# SkyNetV3_1.net
KiCad netlist of a schematic drawn in EAGLE
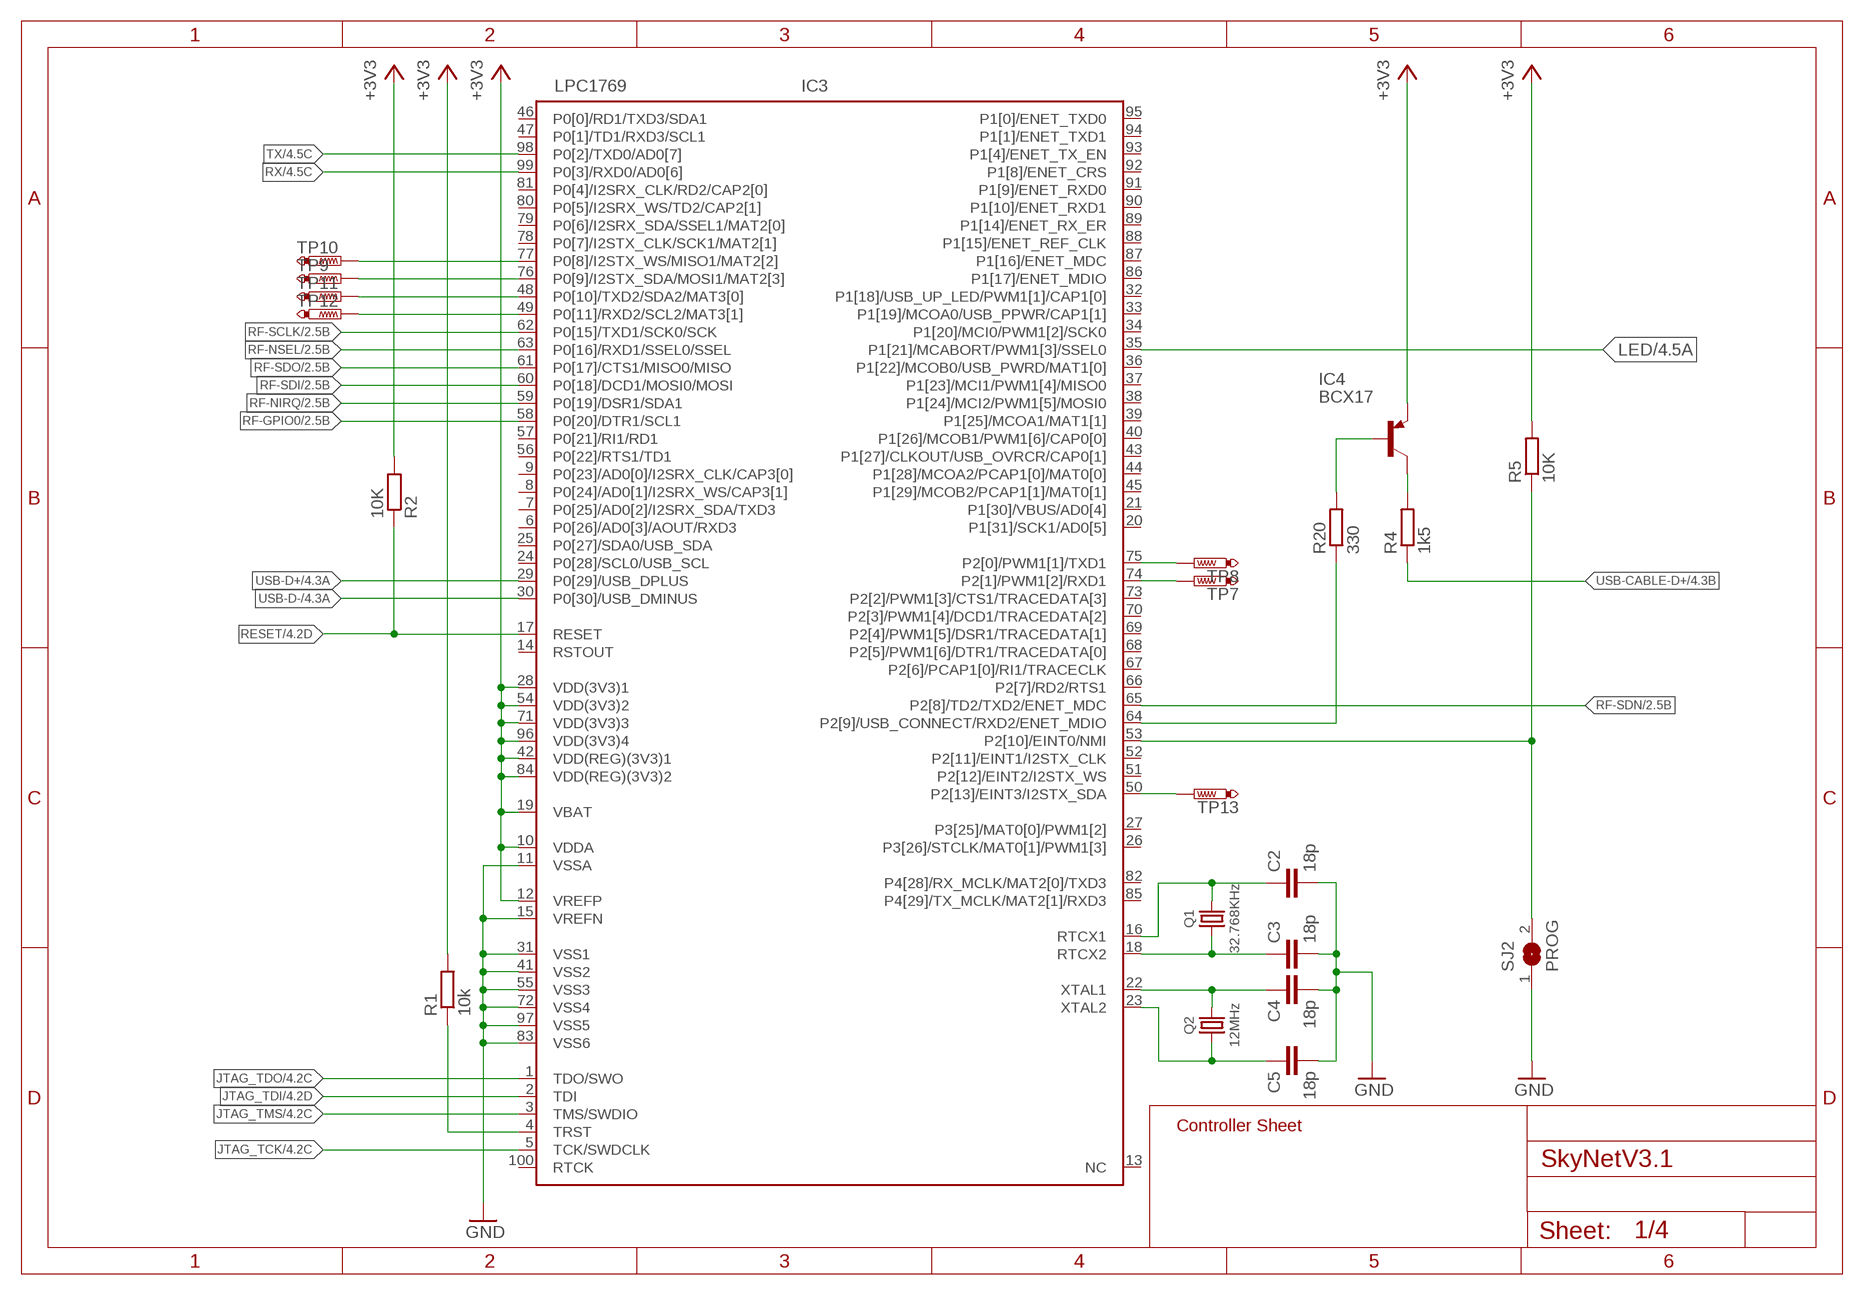
[diagram p0: schematic, sheet 1]
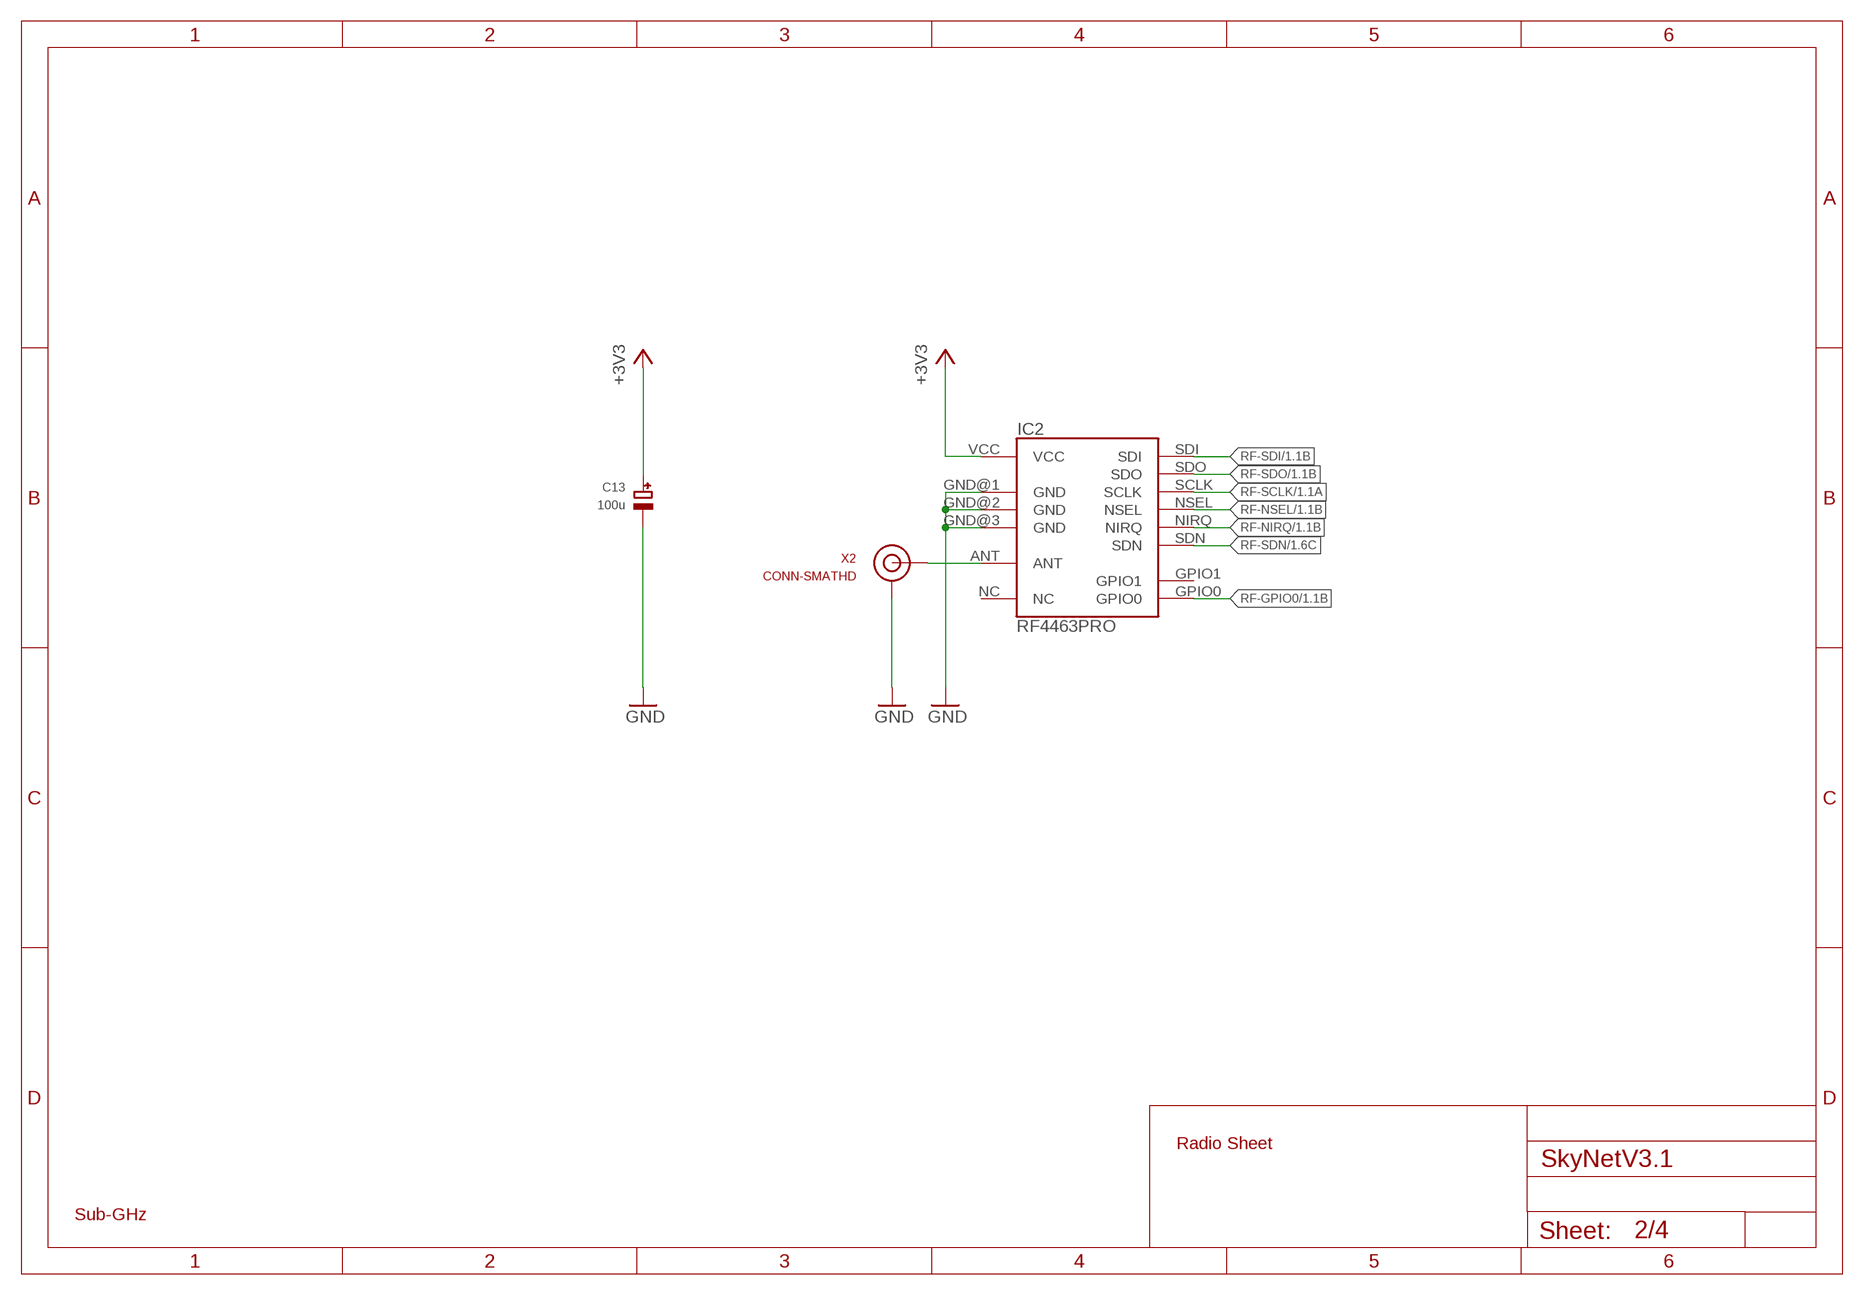
[diagram p1: schematic, sheet 2]
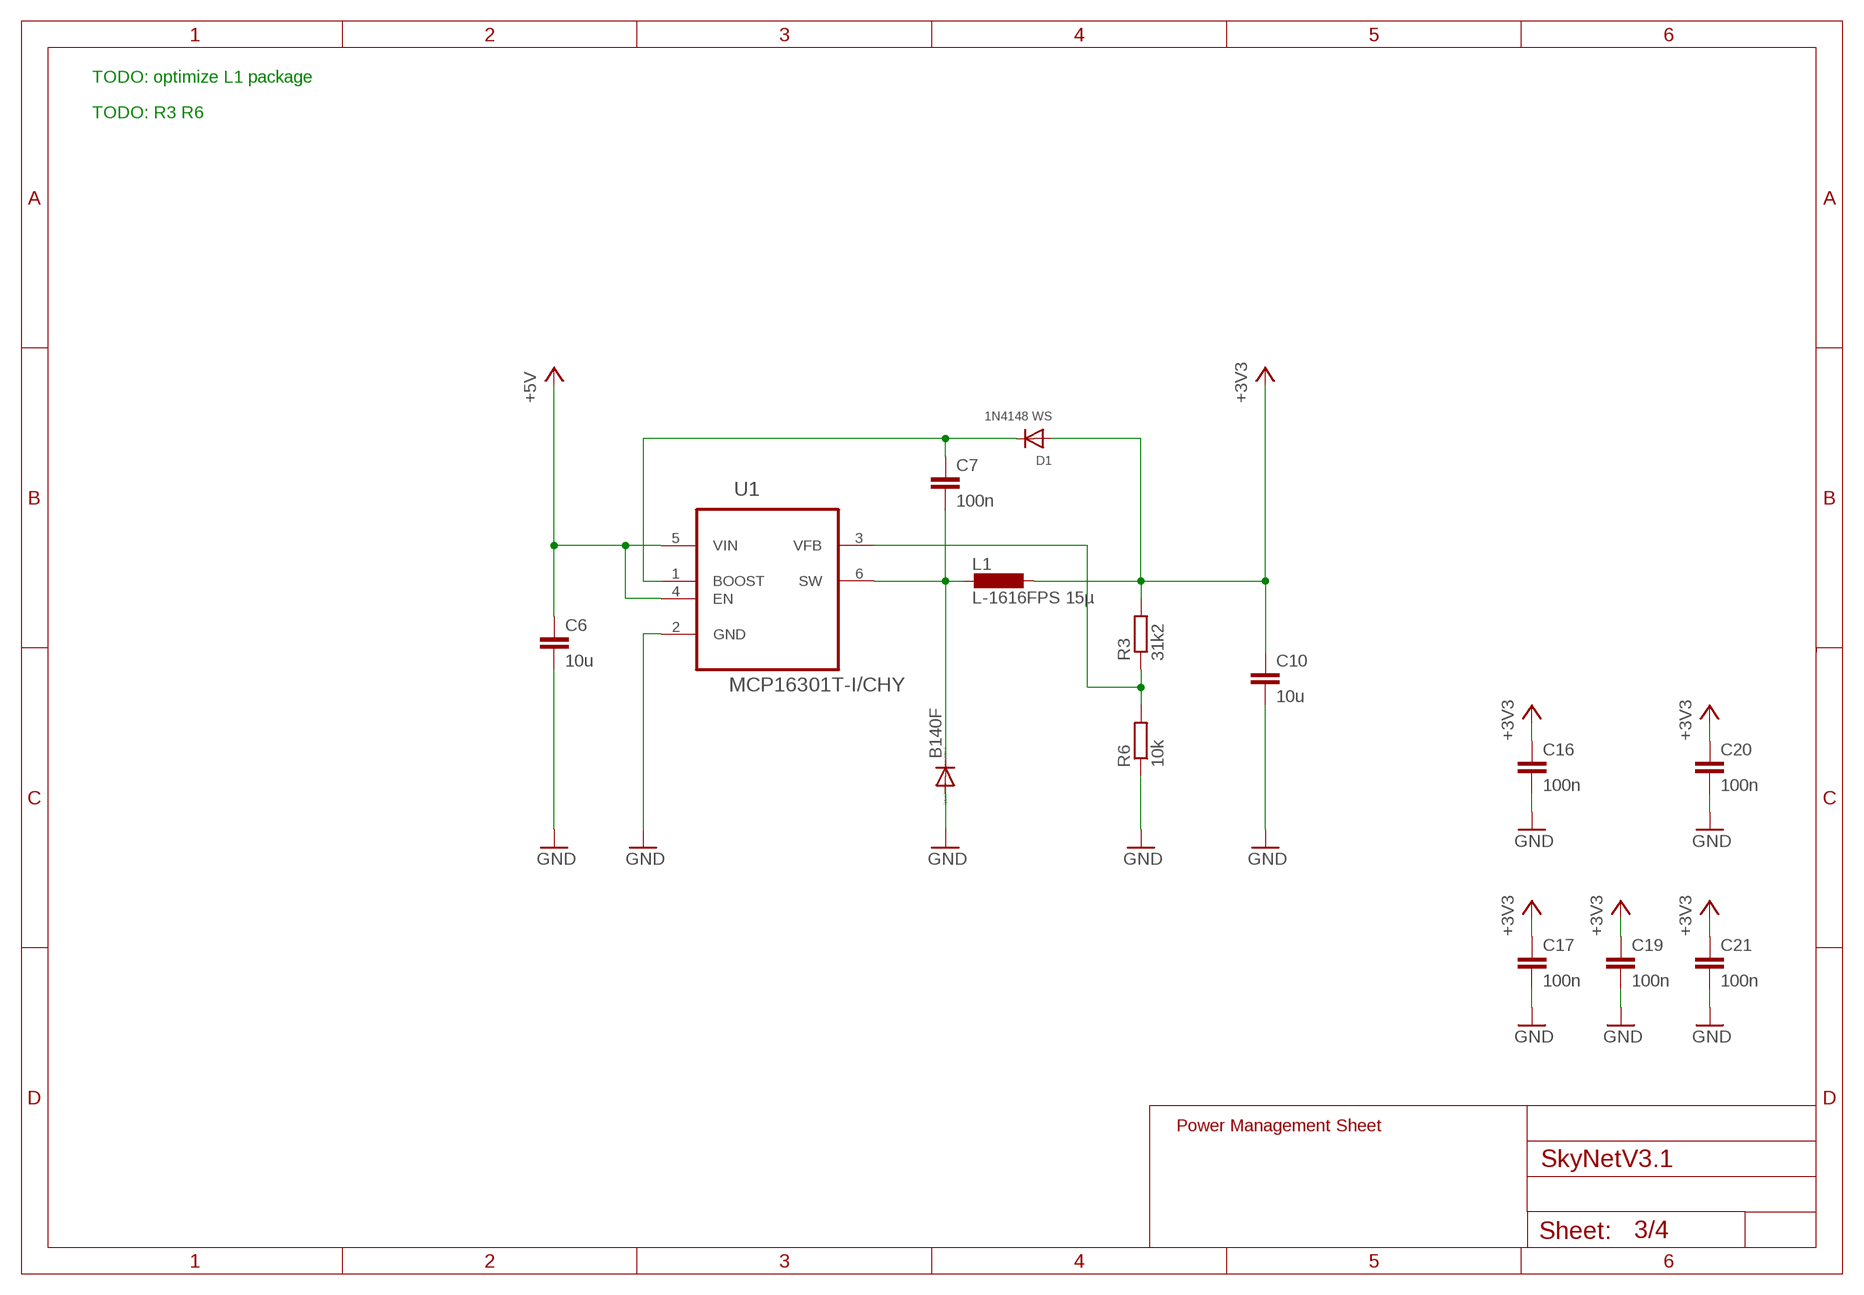
[diagram p2: schematic, sheet 3]
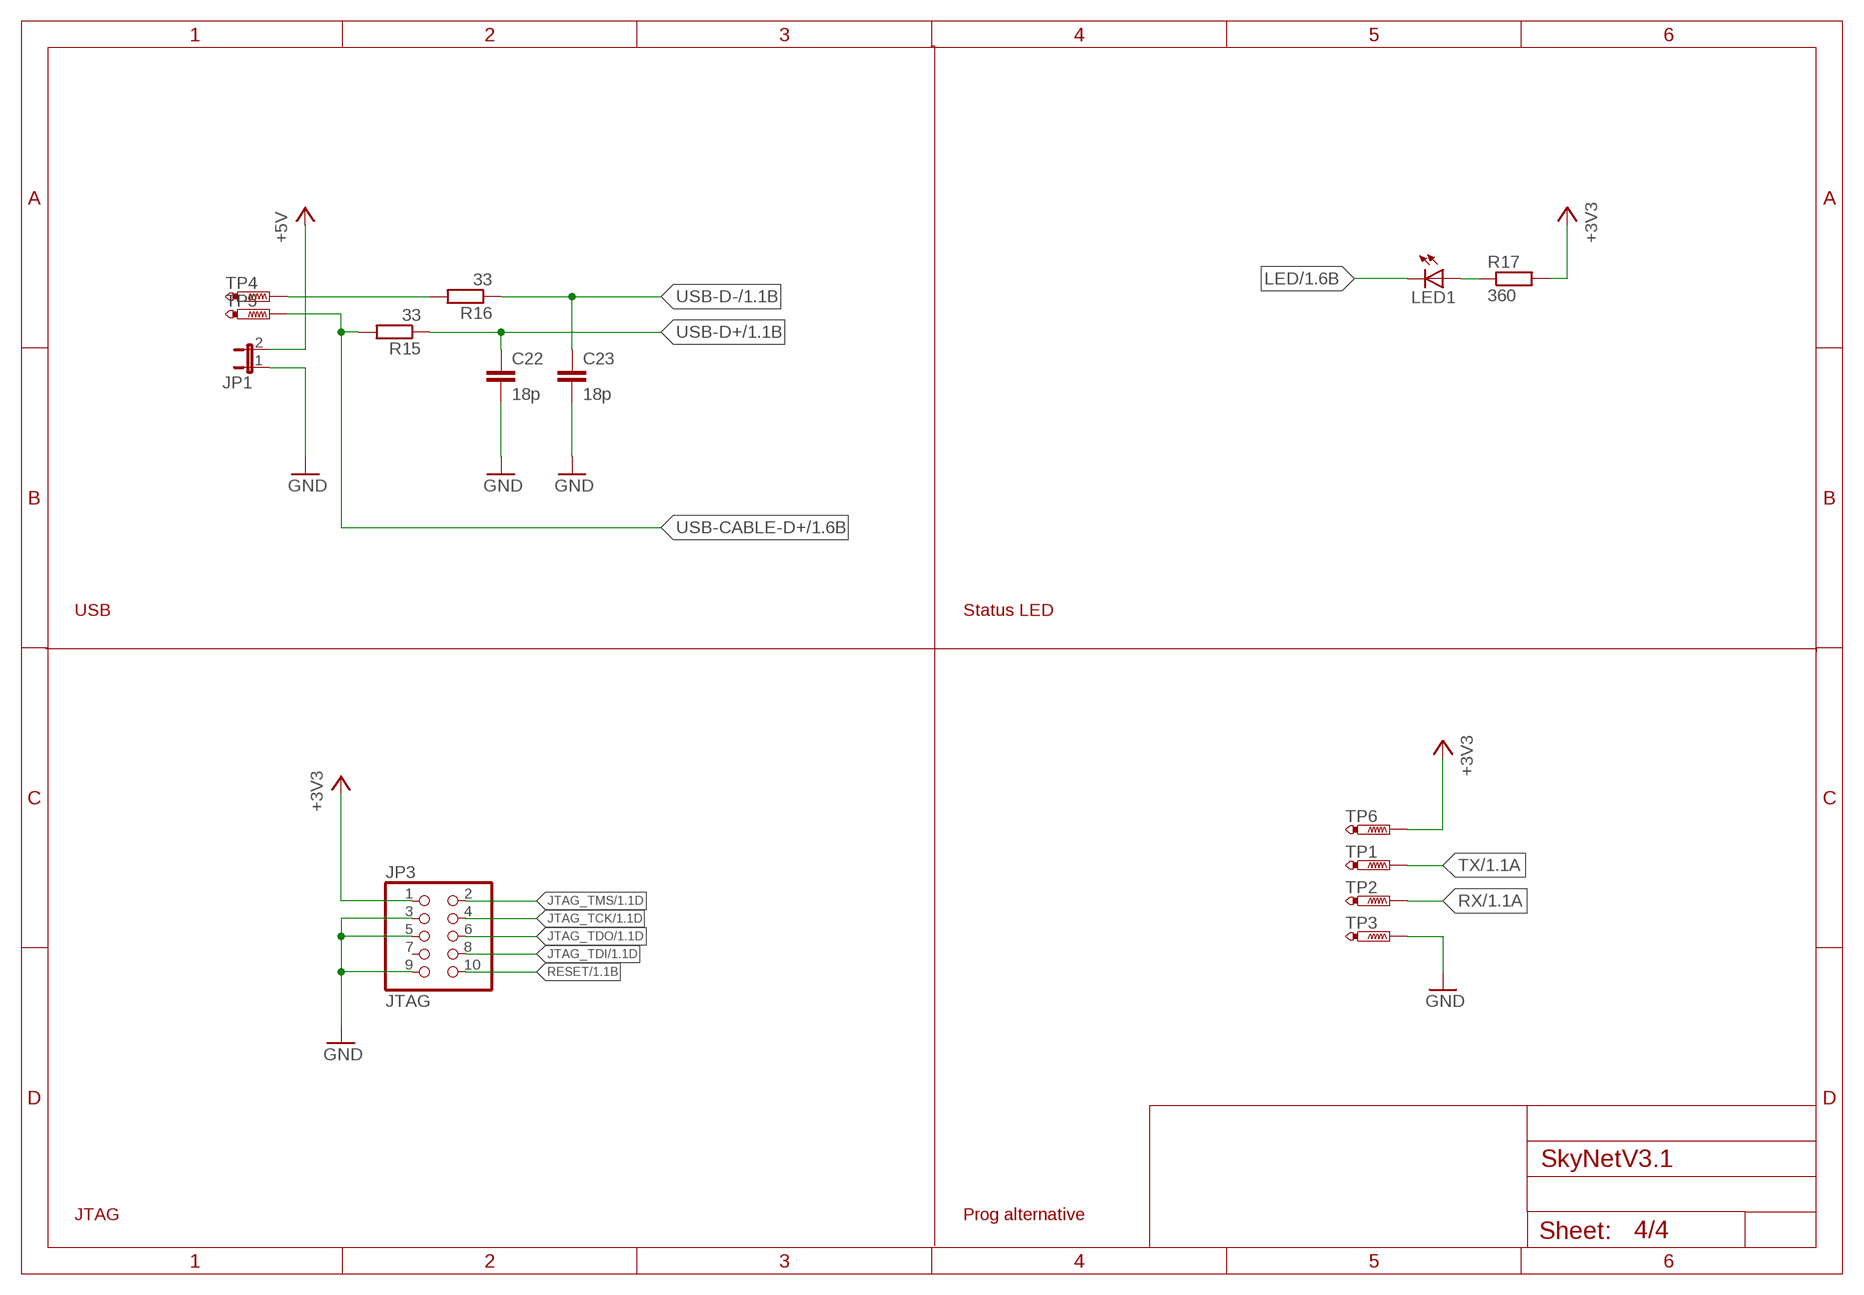
[diagram p3: schematic, sheet 4]

(export (version "E")
  (design (tool "Eeschema 10.0.6"))
  (components
    (comp (ref "C2")
      (value "18p")
      (footprint "eagle-import:C0603")
      (libsource (lib "eagle-import") (part "C-EUC0603"))
    )
    (comp (ref "C3")
      (value "18p")
      (footprint "eagle-import:C0603")
      (libsource (lib "eagle-import") (part "C-EUC0603"))
    )
    (comp (ref "C4")
      (value "18p")
      (footprint "eagle-import:C0603")
      (libsource (lib "eagle-import") (part "C-EUC0603"))
    )
    (comp (ref "C5")
      (value "18p")
      (footprint "eagle-import:C0603")
      (libsource (lib "eagle-import") (part "C-EUC0603"))
    )
    (comp (ref "IC3")
      (value "LPC1769")
      (footprint "eagle-import:LQFP100-14X14")
      (libsource (lib "eagle-import") (part "LPC1768"))
    )
    (comp (ref "IC4")
      (value "BCX17")
      (footprint "eagle-import:SOT23")
      (libsource (lib "eagle-import") (part "BCX17"))
    )
    (comp (ref "Q1")
      (value "32.768KHz")
      (footprint "eagle-import:XTAL_49_18")
      (libsource (lib "eagle-import") (part "XTAL2-PAD"))
    )
    (comp (ref "Q2")
      (value "12MHz")
      (footprint "eagle-import:XTAL_50_32")
      (libsource (lib "eagle-import") (part "XTAL4-PAD"))
    )
    (comp (ref "R1")
      (value "10k")
      (footprint "eagle-import:R0603")
      (libsource (lib "eagle-import") (part "R-EU_R0603"))
    )
    (comp (ref "R2")
      (value "10K")
      (footprint "eagle-import:R0603")
      (libsource (lib "eagle-import") (part "R-EU_R0603"))
    )
    (comp (ref "R4")
      (value "1k5")
      (footprint "eagle-import:R0603")
      (libsource (lib "eagle-import") (part "R-EU_R0603"))
    )
    (comp (ref "R5")
      (value "10K")
      (footprint "eagle-import:R0603")
      (libsource (lib "eagle-import") (part "R-EU_R0603"))
    )
    (comp (ref "R20")
      (value "330")
      (footprint "eagle-import:R0603")
      (libsource (lib "eagle-import") (part "R-EU_R0603"))
    )
    (comp (ref "SJ2")
      (value "PROG")
      (footprint "eagle-import:SJ")
      (libsource (lib "eagle-import") (part "SJ"))
    )
    (comp (ref "TP7")
      (value "PTR1B1,27")
      (footprint "eagle-import:B1,27")
      (libsource (lib "eagle-import") (part "PTR1B1,27"))
    )
    (comp (ref "TP8")
      (value "PTR1B1,27")
      (footprint "eagle-import:B1,27")
      (libsource (lib "eagle-import") (part "PTR1B1,27"))
    )
    (comp (ref "TP9")
      (value "PTR1B1,27")
      (footprint "eagle-import:B1,27")
      (libsource (lib "eagle-import") (part "PTR1B1,27"))
    )
    (comp (ref "TP10")
      (value "PTR1B1,27")
      (footprint "eagle-import:B1,27")
      (libsource (lib "eagle-import") (part "PTR1B1,27"))
    )
    (comp (ref "TP11")
      (value "PTR1B1,27")
      (footprint "eagle-import:B1,27")
      (libsource (lib "eagle-import") (part "PTR1B1,27"))
    )
    (comp (ref "TP12")
      (value "PTR1B1,27")
      (footprint "eagle-import:B1,27")
      (libsource (lib "eagle-import") (part "PTR1B1,27"))
    )
    (comp (ref "TP13")
      (value "PTR1B1,27")
      (footprint "eagle-import:B1,27")
      (libsource (lib "eagle-import") (part "PTR1B1,27"))
    )
    (comp (ref "C13")
      (value "100u")
      (footprint "eagle-import:EIA6032-28_C-W")
      (libsource (lib "eagle-import") (part "CAP_TANTALUMC/6032_WAVE"))
    )
    (comp (ref "IC2")
      (value "RF4463PRO")
      (footprint "eagle-import:STD_BOARD")
      (libsource (lib "eagle-import") (part "RF4463PRO"))
    )
    (comp (ref "X2")
      (value "CONN-SMATHD")
      (footprint "eagle-import:SMA-THD")
      (libsource (lib "eagle-import") (part "CONN-SMATHD"))
    )
    (comp (ref "C22")
      (value "18p")
      (footprint "eagle-import:C0603")
      (libsource (lib "eagle-import") (part "C-EUC0603"))
    )
    (comp (ref "C23")
      (value "18p")
      (footprint "eagle-import:C0603")
      (libsource (lib "eagle-import") (part "C-EUC0603"))
    )
    (comp (ref "JP1")
      (value "JP1E")
      (footprint "eagle-import:JP1")
      (libsource (lib "eagle-import") (part "JP1E"))
    )
    (comp (ref "JP3")
      (value "JTAG")
      (footprint "eagle-import:2X05_1.27MM_SMT")
      (libsource (lib "eagle-import") (part "HEADER-2X51.27MM"))
    )
    (comp (ref "LED1")
      (value "LEDCHIP-LED0805")
      (footprint "eagle-import:CHIP-LED0805")
      (libsource (lib "eagle-import") (part "LEDCHIP-LED0805"))
    )
    (comp (ref "R15")
      (value "33")
      (footprint "eagle-import:R0603")
      (libsource (lib "eagle-import") (part "R-EU_R0603"))
    )
    (comp (ref "R16")
      (value "33")
      (footprint "eagle-import:R0603")
      (libsource (lib "eagle-import") (part "R-EU_R0603"))
    )
    (comp (ref "R17")
      (value "360")
      (footprint "eagle-import:R0603")
      (libsource (lib "eagle-import") (part "R-EU_R0603"))
    )
    (comp (ref "TP1")
      (value "PTR1B1,27")
      (footprint "eagle-import:B1,27")
      (libsource (lib "eagle-import") (part "PTR1B1,27"))
    )
    (comp (ref "TP2")
      (value "PTR1B1,27")
      (footprint "eagle-import:B1,27")
      (libsource (lib "eagle-import") (part "PTR1B1,27"))
    )
    (comp (ref "TP3")
      (value "PTR1B2,54")
      (footprint "eagle-import:B2,54")
      (libsource (lib "eagle-import") (part "PTR1B2,54"))
    )
    (comp (ref "TP4")
      (value "PTR1B1,27")
      (footprint "eagle-import:B1,27")
      (libsource (lib "eagle-import") (part "PTR1B1,27"))
    )
    (comp (ref "TP5")
      (value "PTR1B1,27")
      (footprint "eagle-import:B1,27")
      (libsource (lib "eagle-import") (part "PTR1B1,27"))
    )
    (comp (ref "TP6")
      (value "PTR1B2,54")
      (footprint "eagle-import:B2,54")
      (libsource (lib "eagle-import") (part "PTR1B2,54"))
    )
    (comp (ref "B140F")
      (value "DIODE-DO214AC")
      (footprint "eagle-import:DO214AC")
      (libsource (lib "eagle-import") (part "DIODE-DO214AC"))
    )
    (comp (ref "C6")
      (value "10u")
      (footprint "eagle-import:C0805")
      (libsource (lib "eagle-import") (part "C-EUC0805"))
    )
    (comp (ref "C7")
      (value "100n")
      (footprint "eagle-import:C0603")
      (libsource (lib "eagle-import") (part "C-EUC0603"))
    )
    (comp (ref "C10")
      (value "10u")
      (footprint "eagle-import:C0805")
      (libsource (lib "eagle-import") (part "C-EUC0805"))
    )
    (comp (ref "C16")
      (value "100n")
      (footprint "eagle-import:C0603")
      (libsource (lib "eagle-import") (part "C-EUC0603"))
    )
    (comp (ref "C17")
      (value "100n")
      (footprint "eagle-import:C0603")
      (libsource (lib "eagle-import") (part "C-EUC0603"))
    )
    (comp (ref "C19")
      (value "100n")
      (footprint "eagle-import:C0603")
      (libsource (lib "eagle-import") (part "C-EUC0603"))
    )
    (comp (ref "C20")
      (value "100n")
      (footprint "eagle-import:C0603")
      (libsource (lib "eagle-import") (part "C-EUC0603"))
    )
    (comp (ref "C21")
      (value "100n")
      (footprint "eagle-import:C0603")
      (libsource (lib "eagle-import") (part "C-EUC0603"))
    )
    (comp (ref "D1")
      (value "1N4148 WS")
      (footprint "eagle-import:SOD-323")
      (libsource (lib "eagle-import") (part "DIODESOD-323"))
    )
    (comp (ref "L1")
      (value "L-1616FPS 15µ")
      (footprint "eagle-import:LQH55D")
      (libsource (lib "eagle-import") (part "L-EU2220-LQH55D"))
    )
    (comp (ref "R3")
      (value "31k2")
      (footprint "eagle-import:R0603")
      (libsource (lib "eagle-import") (part "R-EU_R0603"))
    )
    (comp (ref "R6")
      (value "10k")
      (footprint "eagle-import:R0603")
      (libsource (lib "eagle-import") (part "R-EU_R0603"))
    )
    (comp (ref "U1")
      (value "MCP16301T-I/CHY")
      (footprint "eagle-import:SOT95P290X145-6N")
      (libsource (lib "eagle-import") (part "MCP16301T-I/CHY"))
    )
  )
  (nets
    (net (code "1") (name "+3V3") (class "Default")
      (node (ref "C10") (pin "1") (pinfunction "1_1") (pintype "passive"))
      (node (ref "C13") (pin "+") (pinfunction "+_+") (pintype "passive"))
      (node (ref "C16") (pin "1") (pinfunction "1_1") (pintype "passive"))
      (node (ref "C17") (pin "1") (pinfunction "1_1") (pintype "passive"))
      (node (ref "C19") (pin "1") (pinfunction "1_1") (pintype "passive"))
      (node (ref "C20") (pin "1") (pinfunction "1_1") (pintype "passive"))
      (node (ref "C21") (pin "1") (pinfunction "1_1") (pintype "passive"))
      (node (ref "D1") (pin "A") (pinfunction "A_A") (pintype "passive"))
      (node (ref "IC2") (pin "VCC") (pinfunction "VCC_VCC") (pintype "power_in"))
      (node (ref "IC3") (pin "10") (pinfunction "VDDA_10") (pintype "bidirectional"))
      (node (ref "IC3") (pin "12") (pinfunction "VREFP_12") (pintype "bidirectional"))
      (node (ref "IC3") (pin "19") (pinfunction "VBAT_19") (pintype "bidirectional"))
      (node (ref "IC3") (pin "28") (pinfunction "VDD(3V3)1_28") (pintype "bidirectional"))
      (node (ref "IC3") (pin "42") (pinfunction "VDD(REG)(3V3)1_42") (pintype "bidirectional"))
      (node (ref "IC3") (pin "54") (pinfunction "VDD(3V3)2_54") (pintype "bidirectional"))
      (node (ref "IC3") (pin "71") (pinfunction "VDD(3V3)3_71") (pintype "bidirectional"))
      (node (ref "IC3") (pin "84") (pinfunction "VDD(REG)(3V3)2_84") (pintype "bidirectional"))
      (node (ref "IC3") (pin "96") (pinfunction "VDD(3V3)4_96") (pintype "bidirectional"))
      (node (ref "IC4") (pin "2") (pinfunction "E_2") (pintype "passive"))
      (node (ref "JP3") (pin "1") (pinfunction "1_1") (pintype "passive"))
      (node (ref "L1") (pin "P$1") (pinfunction "1_P$1") (pintype "passive"))
      (node (ref "R1") (pin "2") (pinfunction "2_2") (pintype "passive"))
      (node (ref "R17") (pin "2") (pinfunction "2_2") (pintype "passive"))
      (node (ref "R2") (pin "2") (pinfunction "2_2") (pintype "passive"))
      (node (ref "R3") (pin "2") (pinfunction "2_2") (pintype "passive"))
      (node (ref "R5") (pin "2") (pinfunction "2_2") (pintype "passive"))
      (node (ref "TP6") (pin "TP") (pinfunction "TP_TP") (pintype "input"))
    )
    (net (code "2") (name "+5V") (class "Default")
      (node (ref "C6") (pin "1") (pinfunction "1_1") (pintype "passive"))
      (node (ref "JP1") (pin "2") (pinfunction "2_2") (pintype "passive"))
      (node (ref "U1") (pin "4") (pinfunction "EN_4") (pintype "input"))
      (node (ref "U1") (pin "5") (pinfunction "VIN_5") (pintype "input"))
    )
    (net (code "3") (name "GND") (class "Default")
      (node (ref "B140F") (pin "A") (pinfunction "A_A") (pintype "passive"))
      (node (ref "C10") (pin "2") (pinfunction "2_2") (pintype "passive"))
      (node (ref "C13") (pin "-") (pinfunction "-_-") (pintype "passive"))
      (node (ref "C16") (pin "2") (pinfunction "2_2") (pintype "passive"))
      (node (ref "C17") (pin "2") (pinfunction "2_2") (pintype "passive"))
      (node (ref "C19") (pin "2") (pinfunction "2_2") (pintype "passive"))
      (node (ref "C2") (pin "2") (pinfunction "2_2") (pintype "passive"))
      (node (ref "C20") (pin "2") (pinfunction "2_2") (pintype "passive"))
      (node (ref "C21") (pin "2") (pinfunction "2_2") (pintype "passive"))
      (node (ref "C22") (pin "2") (pinfunction "2_2") (pintype "passive"))
      (node (ref "C23") (pin "2") (pinfunction "2_2") (pintype "passive"))
      (node (ref "C3") (pin "2") (pinfunction "2_2") (pintype "passive"))
      (node (ref "C4") (pin "2") (pinfunction "2_2") (pintype "passive"))
      (node (ref "C5") (pin "2") (pinfunction "2_2") (pintype "passive"))
      (node (ref "C6") (pin "2") (pinfunction "2_2") (pintype "passive"))
      (node (ref "IC2") (pin "GND@1") (pinfunction "GND_GND@1") (pintype "power_in"))
      (node (ref "IC2") (pin "GND@2") (pinfunction "GND_GND@2") (pintype "power_in"))
      (node (ref "IC2") (pin "GND@3") (pinfunction "GND_GND@3") (pintype "power_in"))
      (node (ref "IC3") (pin "11") (pinfunction "VSSA_11") (pintype "bidirectional"))
      (node (ref "IC3") (pin "15") (pinfunction "VREFN_15") (pintype "bidirectional"))
      (node (ref "IC3") (pin "31") (pinfunction "VSS1_31") (pintype "bidirectional"))
      (node (ref "IC3") (pin "41") (pinfunction "VSS2_41") (pintype "bidirectional"))
      (node (ref "IC3") (pin "55") (pinfunction "VSS3_55") (pintype "bidirectional"))
      (node (ref "IC3") (pin "72") (pinfunction "VSS4_72") (pintype "bidirectional"))
      (node (ref "IC3") (pin "83") (pinfunction "VSS6_83") (pintype "bidirectional"))
      (node (ref "IC3") (pin "97") (pinfunction "VSS5_97") (pintype "bidirectional"))
      (node (ref "JP1") (pin "1") (pinfunction "1_1") (pintype "passive"))
      (node (ref "JP3") (pin "3") (pinfunction "3_3") (pintype "passive"))
      (node (ref "JP3") (pin "5") (pinfunction "5_5") (pintype "passive"))
      (node (ref "JP3") (pin "9") (pinfunction "9_9") (pintype "passive"))
      (node (ref "R6") (pin "1") (pinfunction "1_1") (pintype "passive"))
      (node (ref "SJ2") (pin "1") (pinfunction "1_1") (pintype "passive"))
      (node (ref "TP3") (pin "TP") (pinfunction "TP_TP") (pintype "input"))
      (node (ref "U1") (pin "2") (pinfunction "GND_2") (pintype "passive"))
      (node (ref "X2") (pin "GND@0") (pinfunction "GND_GND@0") (pintype "bidirectional"))
      (node (ref "X2") (pin "GND@1") (pinfunction "GND_GND@1") (pintype "bidirectional"))
      (node (ref "X2") (pin "GND@2") (pinfunction "GND_GND@2") (pintype "bidirectional"))
      (node (ref "X2") (pin "GND@3") (pinfunction "GND_GND@3") (pintype "bidirectional"))
    )
    (net (code "4") (name "JTAG_TCK") (class "Default")
      (node (ref "IC3") (pin "5") (pinfunction "TCK/SWDCLK_5") (pintype "bidirectional"))
      (node (ref "JP3") (pin "4") (pinfunction "4_4") (pintype "passive"))
    )
    (net (code "5") (name "JTAG_TDI") (class "Default")
      (node (ref "IC3") (pin "2") (pinfunction "TDI_2") (pintype "bidirectional"))
      (node (ref "JP3") (pin "8") (pinfunction "8_8") (pintype "passive"))
    )
    (net (code "6") (name "JTAG_TDO") (class "Default")
      (node (ref "IC3") (pin "1") (pinfunction "TDO/SWO_1") (pintype "bidirectional"))
      (node (ref "JP3") (pin "6") (pinfunction "6_6") (pintype "passive"))
    )
    (net (code "7") (name "JTAG_TMS") (class "Default")
      (node (ref "IC3") (pin "3") (pinfunction "TMS/SWDIO_3") (pintype "bidirectional"))
      (node (ref "JP3") (pin "2") (pinfunction "2_2") (pintype "passive"))
    )
    (net (code "8") (name "LED") (class "Default")
      (node (ref "IC3") (pin "35") (pinfunction "P1[21]/MCABORT/PWM1[3]/SSEL0_35") (pintype "bidirectional"))
      (node (ref "LED1") (pin "C") (pinfunction "C_C") (pintype "passive"))
    )
    (net (code "9") (name "Net-(IC3-P0[8]{slash}I2STX_WS{slash}MISO1{slash}MAT2[2])") (class "Default")
      (node (ref "IC3") (pin "77") (pinfunction "P0[8]/I2STX_WS/MISO1/MAT2[2]_77") (pintype "bidirectional"))
      (node (ref "TP10") (pin "TP") (pinfunction "TP_TP") (pintype "input"))
    )
    (net (code "10") (name "Net-(IC3-P0[9]{slash}I2STX_SDA{slash}MOSI1{slash}MAT2[3])") (class "Default")
      (node (ref "IC3") (pin "76") (pinfunction "P0[9]/I2STX_SDA/MOSI1/MAT2[3]_76") (pintype "bidirectional"))
      (node (ref "TP9") (pin "TP") (pinfunction "TP_TP") (pintype "input"))
    )
    (net (code "11") (name "Net-(IC3-P0[10]{slash}TXD2{slash}SDA2{slash}MAT3[0])") (class "Default")
      (node (ref "IC3") (pin "48") (pinfunction "P0[10]/TXD2/SDA2/MAT3[0]_48") (pintype "bidirectional"))
      (node (ref "TP11") (pin "TP") (pinfunction "TP_TP") (pintype "input"))
    )
    (net (code "12") (name "Net-(IC3-P0[11]{slash}RXD2{slash}SCL2{slash}MAT3[1])") (class "Default")
      (node (ref "IC3") (pin "49") (pinfunction "P0[11]/RXD2/SCL2/MAT3[1]_49") (pintype "bidirectional"))
      (node (ref "TP12") (pin "TP") (pinfunction "TP_TP") (pintype "input"))
    )
    (net (code "13") (name "Net-(IC3-P2[0]{slash}PWM1[1]{slash}TXD1)") (class "Default")
      (node (ref "IC3") (pin "75") (pinfunction "P2[0]/PWM1[1]/TXD1_75") (pintype "bidirectional"))
      (node (ref "TP8") (pin "TP") (pinfunction "TP_TP") (pintype "input"))
    )
    (net (code "14") (name "Net-(IC3-P2[1]{slash}PWM1[2]{slash}RXD1)") (class "Default")
      (node (ref "IC3") (pin "74") (pinfunction "P2[1]/PWM1[2]/RXD1_74") (pintype "bidirectional"))
      (node (ref "TP7") (pin "TP") (pinfunction "TP_TP") (pintype "input"))
    )
    (net (code "15") (name "Net-(IC3-P2[9]{slash}USB_CONNECT{slash}RXD2{slash}ENET_MDIO)") (class "Default")
      (node (ref "IC3") (pin "64") (pinfunction "P2[9]/USB_CONNECT/RXD2/ENET_MDIO_64") (pintype "bidirectional"))
      (node (ref "R20") (pin "1") (pinfunction "1_1") (pintype "passive"))
    )
    (net (code "16") (name "Net-(IC3-P2[10]{slash}EINT0{slash}NMI)") (class "Default")
      (node (ref "IC3") (pin "53") (pinfunction "P2[10]/EINT0/NMI_53") (pintype "bidirectional"))
      (node (ref "R5") (pin "1") (pinfunction "1_1") (pintype "passive"))
      (node (ref "SJ2") (pin "2") (pinfunction "2_2") (pintype "passive"))
    )
    (net (code "17") (name "Net-(IC3-P2[13]{slash}EINT3{slash}I2STX_SDA)") (class "Default")
      (node (ref "IC3") (pin "50") (pinfunction "P2[13]/EINT3/I2STX_SDA_50") (pintype "bidirectional"))
      (node (ref "TP13") (pin "TP") (pinfunction "TP_TP") (pintype "input"))
    )
    (net (code "18") (name "Net-(IC3-RTCX1)") (class "Default")
      (node (ref "C2") (pin "1") (pinfunction "1_1") (pintype "passive"))
      (node (ref "IC3") (pin "16") (pinfunction "RTCX1_16") (pintype "bidirectional"))
      (node (ref "Q1") (pin "2") (pinfunction "2_2") (pintype "passive"))
    )
    (net (code "19") (name "Net-(IC3-RTCX2)") (class "Default")
      (node (ref "C3") (pin "1") (pinfunction "1_1") (pintype "passive"))
      (node (ref "IC3") (pin "18") (pinfunction "RTCX2_18") (pintype "bidirectional"))
      (node (ref "Q1") (pin "1") (pinfunction "1_1") (pintype "passive"))
    )
    (net (code "20") (name "Net-(IC3-TRST)") (class "Default")
      (node (ref "IC3") (pin "4") (pinfunction "TRST_4") (pintype "bidirectional"))
      (node (ref "R1") (pin "1") (pinfunction "1_1") (pintype "passive"))
    )
    (net (code "21") (name "Net-(IC3-XTAL1)") (class "Default")
      (node (ref "C4") (pin "1") (pinfunction "1_1") (pintype "passive"))
      (node (ref "IC3") (pin "22") (pinfunction "XTAL1_22") (pintype "bidirectional"))
      (node (ref "Q2") (pin "3") (pinfunction "2_3") (pintype "passive"))
    )
    (net (code "22") (name "Net-(IC3-XTAL2)") (class "Default")
      (node (ref "C5") (pin "1") (pinfunction "1_1") (pintype "passive"))
      (node (ref "IC3") (pin "23") (pinfunction "XTAL2_23") (pintype "bidirectional"))
      (node (ref "Q2") (pin "1") (pinfunction "1_1") (pintype "passive"))
    )
    (net (code "23") (name "Net-(IC4-B)") (class "Default")
      (node (ref "IC4") (pin "1") (pinfunction "B_1") (pintype "passive"))
      (node (ref "R20") (pin "2") (pinfunction "2_2") (pintype "passive"))
    )
    (net (code "24") (name "Net-(IC4-C)") (class "Default")
      (node (ref "IC4") (pin "3") (pinfunction "C_3") (pintype "passive"))
      (node (ref "R4") (pin "2") (pinfunction "2_2") (pintype "passive"))
    )
    (net (code "25") (name "Net-(L1-2)") (class "Default")
      (node (ref "B140F") (pin "C") (pinfunction "C_C") (pintype "passive"))
      (node (ref "C7") (pin "2") (pinfunction "2_2") (pintype "passive"))
      (node (ref "L1") (pin "P$2") (pinfunction "2_P$2") (pintype "passive"))
      (node (ref "U1") (pin "6") (pinfunction "SW_6") (pintype "output"))
    )
    (net (code "26") (name "Net-(LED1-PadA)") (class "Default")
      (node (ref "LED1") (pin "A") (pinfunction "A_A") (pintype "passive"))
      (node (ref "R17") (pin "1") (pinfunction "1_1") (pintype "passive"))
    )
    (net (code "27") (name "Net-(R16-Pad2)") (class "Default")
      (node (ref "R16") (pin "2") (pinfunction "2_2") (pintype "passive"))
      (node (ref "TP4") (pin "TP") (pinfunction "TP_TP") (pintype "input"))
    )
    (net (code "28") (name "Net-(U1-BOOST)") (class "Default")
      (node (ref "C7") (pin "1") (pinfunction "1_1") (pintype "passive"))
      (node (ref "D1") (pin "C") (pinfunction "C_C") (pintype "passive"))
      (node (ref "U1") (pin "1") (pinfunction "BOOST_1") (pintype "passive"))
    )
    (net (code "29") (name "Net-(U1-VFB)") (class "Default")
      (node (ref "R3") (pin "1") (pinfunction "1_1") (pintype "passive"))
      (node (ref "R6") (pin "2") (pinfunction "2_2") (pintype "passive"))
      (node (ref "U1") (pin "3") (pinfunction "VFB_3") (pintype "output"))
    )
    (net (code "30") (name "Net-(X2-SIGNAL)") (class "Default")
      (node (ref "IC2") (pin "ANT") (pinfunction "ANT_ANT") (pintype "output"))
      (node (ref "X2") (pin "SIG") (pinfunction "SIGNAL_SIG") (pintype "bidirectional"))
    )
    (net (code "31") (name "RESET") (class "Default")
      (node (ref "IC3") (pin "17") (pinfunction "RESET_17") (pintype "bidirectional"))
      (node (ref "JP3") (pin "10") (pinfunction "10_10") (pintype "passive"))
      (node (ref "R2") (pin "1") (pinfunction "1_1") (pintype "passive"))
    )
    (net (code "32") (name "RF-GPIO0") (class "Default")
      (node (ref "IC2") (pin "GPIO0") (pinfunction "GPIO0_GPIO0") (pintype "bidirectional"))
      (node (ref "IC3") (pin "58") (pinfunction "P0[20]/DTR1/SCL1_58") (pintype "bidirectional"))
    )
    (net (code "33") (name "RF-NIRQ") (class "Default")
      (node (ref "IC2") (pin "NIRQ") (pinfunction "NIRQ_NIRQ") (pintype "output"))
      (node (ref "IC3") (pin "59") (pinfunction "P0[19]/DSR1/SDA1_59") (pintype "bidirectional"))
    )
    (net (code "34") (name "RF-NSEL") (class "Default")
      (node (ref "IC2") (pin "NSEL") (pinfunction "NSEL_NSEL") (pintype "input"))
      (node (ref "IC3") (pin "63") (pinfunction "P0[16]/RXD1/SSEL0/SSEL_63") (pintype "bidirectional"))
    )
    (net (code "35") (name "RF-SCLK") (class "Default")
      (node (ref "IC2") (pin "SCLK") (pinfunction "SCLK_SCLK") (pintype "input"))
      (node (ref "IC3") (pin "62") (pinfunction "P0[15]/TXD1/SCK0/SCK_62") (pintype "bidirectional"))
    )
    (net (code "36") (name "RF-SDI") (class "Default")
      (node (ref "IC2") (pin "SDI") (pinfunction "SDI_SDI") (pintype "bidirectional"))
      (node (ref "IC3") (pin "60") (pinfunction "P0[18]/DCD1/MOSI0/MOSI_60") (pintype "bidirectional"))
    )
    (net (code "37") (name "RF-SDN") (class "Default")
      (node (ref "IC2") (pin "SDN") (pinfunction "SDN_SDN") (pintype "input"))
      (node (ref "IC3") (pin "65") (pinfunction "P2[8]/TD2/TXD2/ENET_MDC_65") (pintype "bidirectional"))
    )
    (net (code "38") (name "RF-SDO") (class "Default")
      (node (ref "IC2") (pin "SDO") (pinfunction "SDO_SDO") (pintype "output"))
      (node (ref "IC3") (pin "61") (pinfunction "P0[17]/CTS1/MISO0/MISO_61") (pintype "bidirectional"))
    )
    (net (code "39") (name "RX") (class "Default")
      (node (ref "IC3") (pin "99") (pinfunction "P0[3]/RXD0/AD0[6]_99") (pintype "bidirectional"))
      (node (ref "TP2") (pin "TP") (pinfunction "TP_TP") (pintype "input"))
    )
    (net (code "40") (name "TX") (class "Default")
      (node (ref "IC3") (pin "98") (pinfunction "P0[2]/TXD0/AD0[7]_98") (pintype "bidirectional"))
      (node (ref "TP1") (pin "TP") (pinfunction "TP_TP") (pintype "input"))
    )
    (net (code "41") (name "USB-CABLE-D+") (class "Default")
      (node (ref "R15") (pin "2") (pinfunction "2_2") (pintype "passive"))
      (node (ref "R4") (pin "1") (pinfunction "1_1") (pintype "passive"))
      (node (ref "TP5") (pin "TP") (pinfunction "TP_TP") (pintype "input"))
    )
    (net (code "42") (name "USB-D+") (class "Default")
      (node (ref "C22") (pin "1") (pinfunction "1_1") (pintype "passive"))
      (node (ref "IC3") (pin "29") (pinfunction "P0[29]/USB_DPLUS_29") (pintype "bidirectional"))
      (node (ref "R15") (pin "1") (pinfunction "1_1") (pintype "passive"))
    )
    (net (code "43") (name "USB-D-") (class "Default")
      (node (ref "C23") (pin "1") (pinfunction "1_1") (pintype "passive"))
      (node (ref "IC3") (pin "30") (pinfunction "P0[30]/USB_DMINUS_30") (pintype "bidirectional"))
      (node (ref "R16") (pin "1") (pinfunction "1_1") (pintype "passive"))
    )
    (net (code "44") (name "unconnected-(IC2-PadGPIO1)") (class "Default")
      (node (ref "IC2") (pin "GPIO1") (pinfunction "GPIO1_GPIO1") (pintype "bidirectional"))
    )
    (net (code "45") (name "unconnected-(IC2-PadNC)") (class "Default")
      (node (ref "IC2") (pin "NC") (pinfunction "NC_NC") (pintype "no_connect"))
    )
    (net (code "46") (name "unconnected-(IC3-NC-Pad13)") (class "Default")
      (node (ref "IC3") (pin "13") (pinfunction "NC_13") (pintype "bidirectional"))
    )
    (net (code "47") (name "unconnected-(IC3-P0[0]{slash}RD1{slash}TXD3{slash}SDA1-Pad46)") (class "Default")
      (node (ref "IC3") (pin "46") (pinfunction "P0[0]/RD1/TXD3/SDA1_46") (pintype "bidirectional"))
    )
    (net (code "48") (name "unconnected-(IC3-P0[1]{slash}TD1{slash}RXD3{slash}SCL1-Pad47)") (class "Default")
      (node (ref "IC3") (pin "47") (pinfunction "P0[1]/TD1/RXD3/SCL1_47") (pintype "bidirectional"))
    )
    (net (code "49") (name "unconnected-(IC3-P0[4]{slash}I2SRX_CLK{slash}RD2{slash}CAP2[0]-Pad81)") (class "Default")
      (node (ref "IC3") (pin "81") (pinfunction "P0[4]/I2SRX_CLK/RD2/CAP2[0]_81") (pintype "bidirectional"))
    )
    (net (code "50") (name "unconnected-(IC3-P0[5]{slash}I2SRX_WS{slash}TD2{slash}CAP2[1]-Pad80)") (class "Default")
      (node (ref "IC3") (pin "80") (pinfunction "P0[5]/I2SRX_WS/TD2/CAP2[1]_80") (pintype "bidirectional"))
    )
    (net (code "51") (name "unconnected-(IC3-P0[6]{slash}I2SRX_SDA{slash}SSEL1{slash}MAT2[0]-Pad79)") (class "Default")
      (node (ref "IC3") (pin "79") (pinfunction "P0[6]/I2SRX_SDA/SSEL1/MAT2[0]_79") (pintype "bidirectional"))
    )
    (net (code "52") (name "unconnected-(IC3-P0[7]{slash}I2STX_CLK{slash}SCK1{slash}MAT2[1]-Pad78)") (class "Default")
      (node (ref "IC3") (pin "78") (pinfunction "P0[7]/I2STX_CLK/SCK1/MAT2[1]_78") (pintype "bidirectional"))
    )
    (net (code "53") (name "unconnected-(IC3-P0[21]{slash}RI1{slash}RD1-Pad57)") (class "Default")
      (node (ref "IC3") (pin "57") (pinfunction "P0[21]/RI1/RD1_57") (pintype "bidirectional"))
    )
    (net (code "54") (name "unconnected-(IC3-P0[22]{slash}RTS1{slash}TD1-Pad56)") (class "Default")
      (node (ref "IC3") (pin "56") (pinfunction "P0[22]/RTS1/TD1_56") (pintype "bidirectional"))
    )
    (net (code "55") (name "unconnected-(IC3-P0[23]{slash}AD0[0]{slash}I2SRX_CLK{slash}CAP3[0]-Pad9)") (class "Default")
      (node (ref "IC3") (pin "9") (pinfunction "P0[23]/AD0[0]/I2SRX_CLK/CAP3[0]_9") (pintype "bidirectional"))
    )
    (net (code "56") (name "unconnected-(IC3-P0[24]{slash}AD0[1]{slash}I2SRX_WS{slash}CAP3[1]-Pad8)") (class "Default")
      (node (ref "IC3") (pin "8") (pinfunction "P0[24]/AD0[1]/I2SRX_WS/CAP3[1]_8") (pintype "bidirectional"))
    )
    (net (code "57") (name "unconnected-(IC3-P0[25]{slash}AD0[2]{slash}I2SRX_SDA{slash}TXD3-Pad7)") (class "Default")
      (node (ref "IC3") (pin "7") (pinfunction "P0[25]/AD0[2]/I2SRX_SDA/TXD3_7") (pintype "bidirectional"))
    )
    (net (code "58") (name "unconnected-(IC3-P0[26]{slash}AD0[3]{slash}AOUT{slash}RXD3-Pad6)") (class "Default")
      (node (ref "IC3") (pin "6") (pinfunction "P0[26]/AD0[3]/AOUT/RXD3_6") (pintype "bidirectional"))
    )
    (net (code "59") (name "unconnected-(IC3-P0[27]{slash}SDA0{slash}USB_SDA-Pad25)") (class "Default")
      (node (ref "IC3") (pin "25") (pinfunction "P0[27]/SDA0/USB_SDA_25") (pintype "bidirectional"))
    )
    (net (code "60") (name "unconnected-(IC3-P0[28]{slash}SCL0{slash}USB_SCL-Pad24)") (class "Default")
      (node (ref "IC3") (pin "24") (pinfunction "P0[28]/SCL0/USB_SCL_24") (pintype "bidirectional"))
    )
    (net (code "61") (name "unconnected-(IC3-P1[0]{slash}ENET_TXD0-Pad95)") (class "Default")
      (node (ref "IC3") (pin "95") (pinfunction "P1[0]/ENET_TXD0_95") (pintype "bidirectional"))
    )
    (net (code "62") (name "unconnected-(IC3-P1[1]{slash}ENET_TXD1-Pad94)") (class "Default")
      (node (ref "IC3") (pin "94") (pinfunction "P1[1]/ENET_TXD1_94") (pintype "bidirectional"))
    )
    (net (code "63") (name "unconnected-(IC3-P1[4]{slash}ENET_TX_EN-Pad93)") (class "Default")
      (node (ref "IC3") (pin "93") (pinfunction "P1[4]/ENET_TX_EN_93") (pintype "bidirectional"))
    )
    (net (code "64") (name "unconnected-(IC3-P1[8]{slash}ENET_CRS-Pad92)") (class "Default")
      (node (ref "IC3") (pin "92") (pinfunction "P1[8]/ENET_CRS_92") (pintype "bidirectional"))
    )
    (net (code "65") (name "unconnected-(IC3-P1[9]{slash}ENET_RXD0-Pad91)") (class "Default")
      (node (ref "IC3") (pin "91") (pinfunction "P1[9]/ENET_RXD0_91") (pintype "bidirectional"))
    )
    (net (code "66") (name "unconnected-(IC3-P1[10]{slash}ENET_RXD1-Pad90)") (class "Default")
      (node (ref "IC3") (pin "90") (pinfunction "P1[10]/ENET_RXD1_90") (pintype "bidirectional"))
    )
    (net (code "67") (name "unconnected-(IC3-P1[14]{slash}ENET_RX_ER-Pad89)") (class "Default")
      (node (ref "IC3") (pin "89") (pinfunction "P1[14]/ENET_RX_ER_89") (pintype "bidirectional"))
    )
    (net (code "68") (name "unconnected-(IC3-P1[15]{slash}ENET_REF_CLK-Pad88)") (class "Default")
      (node (ref "IC3") (pin "88") (pinfunction "P1[15]/ENET_REF_CLK_88") (pintype "bidirectional"))
    )
    (net (code "69") (name "unconnected-(IC3-P1[16]{slash}ENET_MDC-Pad87)") (class "Default")
      (node (ref "IC3") (pin "87") (pinfunction "P1[16]/ENET_MDC_87") (pintype "bidirectional"))
    )
    (net (code "70") (name "unconnected-(IC3-P1[17]{slash}ENET_MDIO-Pad86)") (class "Default")
      (node (ref "IC3") (pin "86") (pinfunction "P1[17]/ENET_MDIO_86") (pintype "bidirectional"))
    )
    (net (code "71") (name "unconnected-(IC3-P1[18]{slash}USB_UP_LED{slash}PWM1[1]{slash}CAP1[0]-Pad32)") (class "Default")
      (node (ref "IC3") (pin "32") (pinfunction "P1[18]/USB_UP_LED/PWM1[1]/CAP1[0]_32") (pintype "bidirectional"))
    )
    (net (code "72") (name "unconnected-(IC3-P1[19]{slash}MCOA0{slash}USB_PPWR{slash}CAP1[1]-Pad33)") (class "Default")
      (node (ref "IC3") (pin "33") (pinfunction "P1[19]/MCOA0/USB_PPWR/CAP1[1]_33") (pintype "bidirectional"))
    )
    (net (code "73") (name "unconnected-(IC3-P1[20]{slash}MCI0{slash}PWM1[2]{slash}SCK0-Pad34)") (class "Default")
      (node (ref "IC3") (pin "34") (pinfunction "P1[20]/MCI0/PWM1[2]/SCK0_34") (pintype "bidirectional"))
    )
    (net (code "74") (name "unconnected-(IC3-P1[22]{slash}MCOB0{slash}USB_PWRD{slash}MAT1[0]-Pad36)") (class "Default")
      (node (ref "IC3") (pin "36") (pinfunction "P1[22]/MCOB0/USB_PWRD/MAT1[0]_36") (pintype "bidirectional"))
    )
    (net (code "75") (name "unconnected-(IC3-P1[23]{slash}MCI1{slash}PWM1[4]{slash}MISO0-Pad37)") (class "Default")
      (node (ref "IC3") (pin "37") (pinfunction "P1[23]/MCI1/PWM1[4]/MISO0_37") (pintype "bidirectional"))
    )
    (net (code "76") (name "unconnected-(IC3-P1[24]{slash}MCI2{slash}PWM1[5]{slash}MOSI0-Pad38)") (class "Default")
      (node (ref "IC3") (pin "38") (pinfunction "P1[24]/MCI2/PWM1[5]/MOSI0_38") (pintype "bidirectional"))
    )
    (net (code "77") (name "unconnected-(IC3-P1[25]{slash}MCOA1{slash}MAT1[1]-Pad39)") (class "Default")
      (node (ref "IC3") (pin "39") (pinfunction "P1[25]/MCOA1/MAT1[1]_39") (pintype "bidirectional"))
    )
    (net (code "78") (name "unconnected-(IC3-P1[26]{slash}MCOB1{slash}PWM1[6]{slash}CAP0[0]-Pad40)") (class "Default")
      (node (ref "IC3") (pin "40") (pinfunction "P1[26]/MCOB1/PWM1[6]/CAP0[0]_40") (pintype "bidirectional"))
    )
    (net (code "79") (name "unconnected-(IC3-P1[27]{slash}CLKOUT{slash}USB_OVRCR{slash}CAP0[1]-Pad43)") (class "Default")
      (node (ref "IC3") (pin "43") (pinfunction "P1[27]/CLKOUT/USB_OVRCR/CAP0[1]_43") (pintype "bidirectional"))
    )
    (net (code "80") (name "unconnected-(IC3-P1[28]{slash}MCOA2{slash}PCAP1[0]{slash}MAT0[0]-Pad44)") (class "Default")
      (node (ref "IC3") (pin "44") (pinfunction "P1[28]/MCOA2/PCAP1[0]/MAT0[0]_44") (pintype "bidirectional"))
    )
    (net (code "81") (name "unconnected-(IC3-P1[29]{slash}MCOB2{slash}PCAP1[1]{slash}MAT0[1]-Pad45)") (class "Default")
      (node (ref "IC3") (pin "45") (pinfunction "P1[29]/MCOB2/PCAP1[1]/MAT0[1]_45") (pintype "bidirectional"))
    )
    (net (code "82") (name "unconnected-(IC3-P1[30]{slash}VBUS{slash}AD0[4]-Pad21)") (class "Default")
      (node (ref "IC3") (pin "21") (pinfunction "P1[30]/VBUS/AD0[4]_21") (pintype "bidirectional"))
    )
    (net (code "83") (name "unconnected-(IC3-P1[31]{slash}SCK1{slash}AD0[5]-Pad20)") (class "Default")
      (node (ref "IC3") (pin "20") (pinfunction "P1[31]/SCK1/AD0[5]_20") (pintype "bidirectional"))
    )
    (net (code "84") (name "unconnected-(IC3-P2[2]{slash}PWM1[3]{slash}CTS1{slash}TRACEDATA[3]-Pad73)") (class "Default")
      (node (ref "IC3") (pin "73") (pinfunction "P2[2]/PWM1[3]/CTS1/TRACEDATA[3]_73") (pintype "bidirectional"))
    )
    (net (code "85") (name "unconnected-(IC3-P2[3]{slash}PWM1[4]{slash}DCD1{slash}TRACEDATA[2]-Pad70)") (class "Default")
      (node (ref "IC3") (pin "70") (pinfunction "P2[3]/PWM1[4]/DCD1/TRACEDATA[2]_70") (pintype "bidirectional"))
    )
    (net (code "86") (name "unconnected-(IC3-P2[4]{slash}PWM1[5]{slash}DSR1{slash}TRACEDATA[1]-Pad69)") (class "Default")
      (node (ref "IC3") (pin "69") (pinfunction "P2[4]/PWM1[5]/DSR1/TRACEDATA[1]_69") (pintype "bidirectional"))
    )
    (net (code "87") (name "unconnected-(IC3-P2[5]{slash}PWM1[6]{slash}DTR1{slash}TRACEDATA[0]-Pad68)") (class "Default")
      (node (ref "IC3") (pin "68") (pinfunction "P2[5]/PWM1[6]/DTR1/TRACEDATA[0]_68") (pintype "bidirectional"))
    )
    (net (code "88") (name "unconnected-(IC3-P2[6]{slash}PCAP1[0]{slash}RI1{slash}TRACECLK-Pad67)") (class "Default")
      (node (ref "IC3") (pin "67") (pinfunction "P2[6]/PCAP1[0]/RI1/TRACECLK_67") (pintype "bidirectional"))
    )
    (net (code "89") (name "unconnected-(IC3-P2[7]{slash}RD2{slash}RTS1-Pad66)") (class "Default")
      (node (ref "IC3") (pin "66") (pinfunction "P2[7]/RD2/RTS1_66") (pintype "bidirectional"))
    )
    (net (code "90") (name "unconnected-(IC3-P2[11]{slash}EINT1{slash}I2STX_CLK-Pad52)") (class "Default")
      (node (ref "IC3") (pin "52") (pinfunction "P2[11]/EINT1/I2STX_CLK_52") (pintype "bidirectional"))
    )
    (net (code "91") (name "unconnected-(IC3-P2[12]{slash}EINT2{slash}I2STX_WS-Pad51)") (class "Default")
      (node (ref "IC3") (pin "51") (pinfunction "P2[12]/EINT2/I2STX_WS_51") (pintype "bidirectional"))
    )
    (net (code "92") (name "unconnected-(IC3-P3[25]{slash}MAT0[0]{slash}PWM1[2]-Pad27)") (class "Default")
      (node (ref "IC3") (pin "27") (pinfunction "P3[25]/MAT0[0]/PWM1[2]_27") (pintype "bidirectional"))
    )
    (net (code "93") (name "unconnected-(IC3-P3[26]{slash}STCLK{slash}MAT0[1]{slash}PWM1[3]-Pad26)") (class "Default")
      (node (ref "IC3") (pin "26") (pinfunction "P3[26]/STCLK/MAT0[1]/PWM1[3]_26") (pintype "bidirectional"))
    )
    (net (code "94") (name "unconnected-(IC3-P4[28]{slash}RX_MCLK{slash}MAT2[0]{slash}TXD3-Pad82)") (class "Default")
      (node (ref "IC3") (pin "82") (pinfunction "P4[28]/RX_MCLK/MAT2[0]/TXD3_82") (pintype "bidirectional"))
    )
    (net (code "95") (name "unconnected-(IC3-P4[29]{slash}TX_MCLK{slash}MAT2[1]{slash}RXD3-Pad85)") (class "Default")
      (node (ref "IC3") (pin "85") (pinfunction "P4[29]/TX_MCLK/MAT2[1]/RXD3_85") (pintype "bidirectional"))
    )
    (net (code "96") (name "unconnected-(IC3-RSTOUT-Pad14)") (class "Default")
      (node (ref "IC3") (pin "14") (pinfunction "RSTOUT_14") (pintype "bidirectional"))
    )
    (net (code "97") (name "unconnected-(IC3-RTCK-Pad100)") (class "Default")
      (node (ref "IC3") (pin "100") (pinfunction "RTCK_100") (pintype "bidirectional"))
    )
    (net (code "98") (name "unconnected-(JP3-Pad7)") (class "Default")
      (node (ref "JP3") (pin "7") (pinfunction "7_7") (pintype "passive"))
    )
  )
)
